# schematic.net
KiCad netlist of a schematic drawn in EAGLE
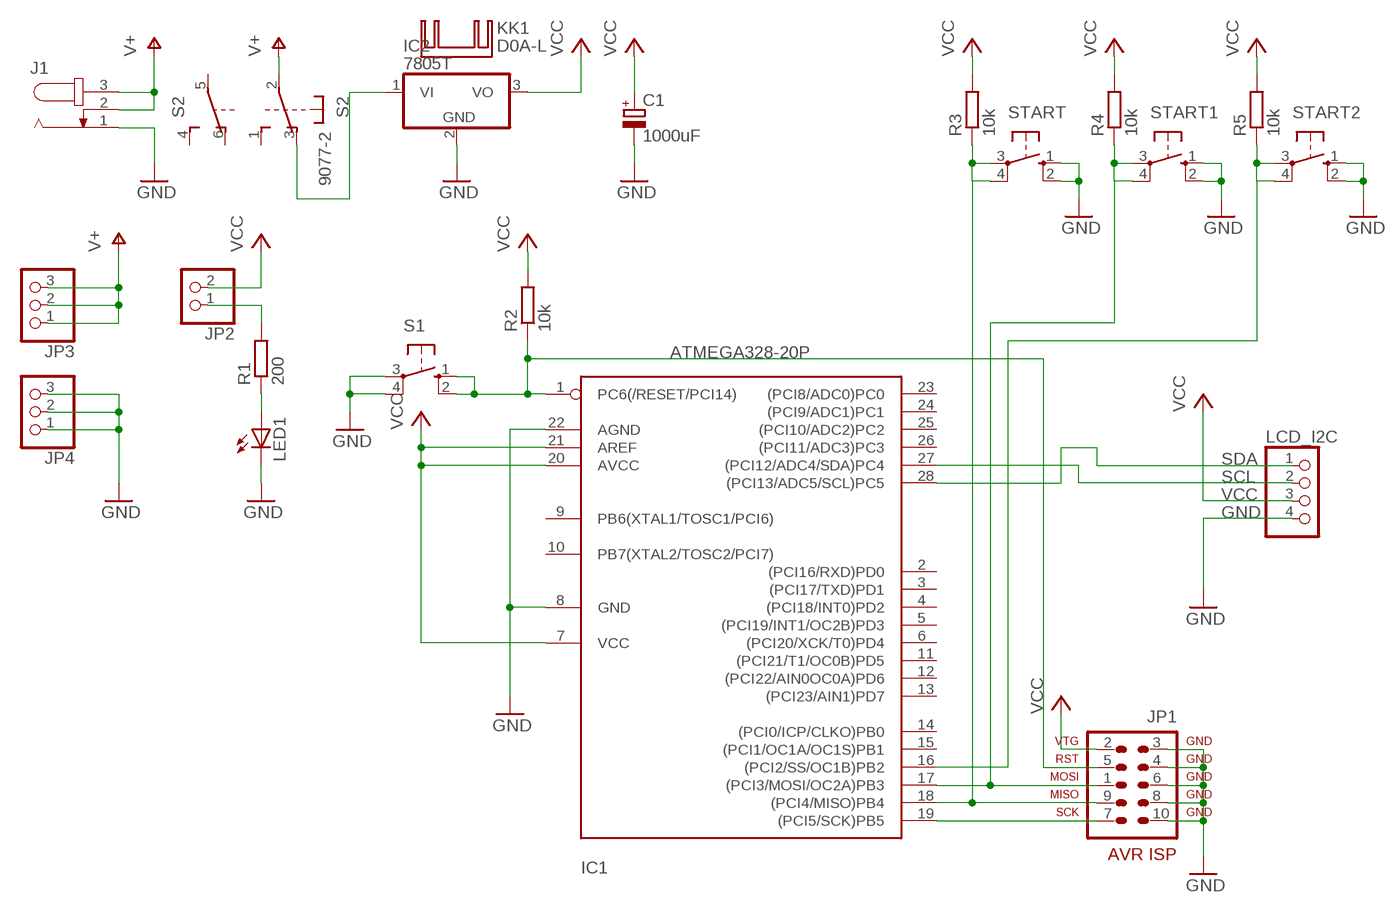
[diagram p0: schematic, sheet 1]

(export (version "E")
  (design (tool "Eeschema 10.0.6"))
  (components
    (comp (ref "C1")
      (value "1000uF")
      (footprint "eagle-import:E3,5-10")
      (libsource (lib "eagle-import") (part "CPOL-EUE3.5-10"))
    )
    (comp (ref "IC1")
      (value "ATMEGA328-20P")
      (footprint "eagle-import:DIL28-3")
      (libsource (lib "eagle-import") (part "ATMEGA328P-20"))
    )
    (comp (ref "IC2")
      (value "7805T")
      (footprint "eagle-import:TO220H")
      (libsource (lib "eagle-import") (part "78T05"))
    )
    (comp (ref "J1")
      (value "JACK-PLUG0")
      (footprint "eagle-import:SPC4077")
      (libsource (lib "eagle-import") (part "JACK-PLUG0"))
    )
    (comp (ref "JP1")
      (value "AVR-ISP-10")
      (footprint "eagle-import:AVR-ISP-10")
      (libsource (lib "eagle-import") (part "AVR-ISP-10"))
    )
    (comp (ref "JP2")
      (value "PINHD-1X2")
      (footprint "eagle-import:1X02")
      (libsource (lib "eagle-import") (part "PINHD-1X2"))
    )
    (comp (ref "JP3")
      (value "PINHD-1X3")
      (footprint "eagle-import:1X03")
      (libsource (lib "eagle-import") (part "PINHD-1X3"))
    )
    (comp (ref "JP4")
      (value "PINHD-1X3")
      (footprint "eagle-import:1X03")
      (libsource (lib "eagle-import") (part "PINHD-1X3"))
    )
    (comp (ref "KK1")
      (value "D0A-L")
      (footprint "eagle-import:D02A-L")
      (libsource (lib "eagle-import") (part "D0A-L"))
    )
    (comp (ref "LCD_I2C")
      (value "PINHD-1X4")
      (footprint "eagle-import:1X04")
      (libsource (lib "eagle-import") (part "PINHD-1X4"))
    )
    (comp (ref "LED1")
      (value "LED5MM")
      (footprint "eagle-import:LED5MM")
      (libsource (lib "eagle-import") (part "LED5MM"))
    )
    (comp (ref "R1")
      (value "200")
      (footprint "eagle-import:0207_10")
      (libsource (lib "eagle-import") (part "R-EU_0207/10"))
    )
    (comp (ref "R2")
      (value "10k")
      (footprint "eagle-import:0207_10")
      (libsource (lib "eagle-import") (part "R-EU_0207/10"))
    )
    (comp (ref "R3")
      (value "10k")
      (footprint "eagle-import:0207_10")
      (libsource (lib "eagle-import") (part "R-EU_0207/10"))
    )
    (comp (ref "R4")
      (value "10k")
      (footprint "eagle-import:0207_10")
      (libsource (lib "eagle-import") (part "R-EU_0207/10"))
    )
    (comp (ref "R5")
      (value "10k")
      (footprint "eagle-import:0207_10")
      (libsource (lib "eagle-import") (part "R-EU_0207/10"))
    )
    (comp (ref "S1")
      (value "10-XX")
      (footprint "eagle-import:B3F-10XX")
      (fields (field (name "MPN") "B3F-1000"))
      (libsource (lib "eagle-import") (part "10-XX"))
    )
    (comp (ref "S2")
      (value "9077-2")
      (footprint "eagle-import:9077-2")
      (libsource (lib "eagle-import") (part "9077-2"))
    )
    (comp (ref "START")
      (value "10-XX")
      (footprint "eagle-import:B3F-10XX")
      (fields (field (name "MPN") "B3F-1000"))
      (libsource (lib "eagle-import") (part "10-XX"))
    )
    (comp (ref "START1")
      (value "10-XX")
      (footprint "eagle-import:B3F-10XX")
      (fields (field (name "MPN") "B3F-1000"))
      (libsource (lib "eagle-import") (part "10-XX"))
    )
    (comp (ref "START2")
      (value "10-XX")
      (footprint "eagle-import:B3F-10XX")
      (fields (field (name "MPN") "B3F-1000"))
      (libsource (lib "eagle-import") (part "10-XX"))
    )
  )
  (nets
    (net (code "1") (name "/SCL") (class "Default")
      (node (ref "IC1") (pin "27") (pinfunction "(PCI12/ADC4/SDA)PC4_27") (pintype "bidirectional"))
      (node (ref "LCD_I2C") (pin "2") (pinfunction "2_2") (pintype "passive"))
    )
    (net (code "2") (name "/SDA") (class "Default")
      (node (ref "IC1") (pin "28") (pinfunction "(PCI13/ADC5/SCL)PC5_28") (pintype "bidirectional"))
      (node (ref "LCD_I2C") (pin "1") (pinfunction "1_1") (pintype "passive"))
    )
    (net (code "3") (name "GND") (class "Default")
      (node (ref "C1") (pin "-") (pinfunction "-_-") (pintype "passive"))
      (node (ref "IC1") (pin "22") (pinfunction "AGND_22") (pintype "bidirectional"))
      (node (ref "IC1") (pin "8") (pinfunction "GND_8") (pintype "bidirectional"))
      (node (ref "IC2") (pin "2") (pinfunction "GND_2") (pintype "passive"))
      (node (ref "J1") (pin "1") (pinfunction "1_1") (pintype "passive"))
      (node (ref "JP1") (pin "10") (pinfunction "10_10") (pintype "passive"))
      (node (ref "JP1") (pin "3") (pinfunction "3_3") (pintype "passive"))
      (node (ref "JP1") (pin "4") (pinfunction "4_4") (pintype "passive"))
      (node (ref "JP1") (pin "6") (pinfunction "6_6") (pintype "passive"))
      (node (ref "JP1") (pin "8") (pinfunction "8_8") (pintype "passive"))
      (node (ref "JP4") (pin "1") (pinfunction "1_1") (pintype "passive"))
      (node (ref "JP4") (pin "2") (pinfunction "2_2") (pintype "passive"))
      (node (ref "JP4") (pin "3") (pinfunction "3_3") (pintype "passive"))
      (node (ref "LCD_I2C") (pin "4") (pinfunction "4_4") (pintype "passive"))
      (node (ref "LED1") (pin "K") (pinfunction "C_K") (pintype "passive"))
      (node (ref "S1") (pin "3") (pinfunction "P_3") (pintype "passive"))
      (node (ref "S1") (pin "4") (pinfunction "P1_4") (pintype "passive"))
      (node (ref "START") (pin "1") (pinfunction "S_1") (pintype "passive"))
      (node (ref "START") (pin "2") (pinfunction "S1_2") (pintype "passive"))
      (node (ref "START1") (pin "1") (pinfunction "S_1") (pintype "passive"))
      (node (ref "START1") (pin "2") (pinfunction "S1_2") (pintype "passive"))
      (node (ref "START2") (pin "1") (pinfunction "S_1") (pintype "passive"))
      (node (ref "START2") (pin "2") (pinfunction "S1_2") (pintype "passive"))
    )
    (net (code "4") (name "Net-(IC1-(PCI2{slash}SS{slash}OC1B)PB2)") (class "Default")
      (node (ref "IC1") (pin "16") (pinfunction "(PCI2/SS/OC1B)PB2_16") (pintype "bidirectional"))
      (node (ref "R5") (pin "1") (pinfunction "1_1") (pintype "passive"))
      (node (ref "START2") (pin "3") (pinfunction "P_3") (pintype "passive"))
      (node (ref "START2") (pin "4") (pinfunction "P1_4") (pintype "passive"))
    )
    (net (code "5") (name "Net-(IC1-(PCI3{slash}MOSI{slash}OC2A)PB3)") (class "Default")
      (node (ref "IC1") (pin "17") (pinfunction "(PCI3/MOSI/OC2A)PB3_17") (pintype "bidirectional"))
      (node (ref "JP1") (pin "1") (pinfunction "1_1") (pintype "passive"))
      (node (ref "R4") (pin "1") (pinfunction "1_1") (pintype "passive"))
      (node (ref "START1") (pin "3") (pinfunction "P_3") (pintype "passive"))
      (node (ref "START1") (pin "4") (pinfunction "P1_4") (pintype "passive"))
    )
    (net (code "6") (name "Net-(IC1-(PCI4{slash}MISO)PB4)") (class "Default")
      (node (ref "IC1") (pin "18") (pinfunction "(PCI4/MISO)PB4_18") (pintype "bidirectional"))
      (node (ref "JP1") (pin "9") (pinfunction "9_9") (pintype "passive"))
      (node (ref "R3") (pin "1") (pinfunction "1_1") (pintype "passive"))
      (node (ref "START") (pin "3") (pinfunction "P_3") (pintype "passive"))
      (node (ref "START") (pin "4") (pinfunction "P1_4") (pintype "passive"))
    )
    (net (code "7") (name "Net-(IC1-(PCI5{slash}SCK)PB5)") (class "Default")
      (node (ref "IC1") (pin "19") (pinfunction "(PCI5/SCK)PB5_19") (pintype "bidirectional"))
      (node (ref "JP1") (pin "7") (pinfunction "7_7") (pintype "passive"))
    )
    (net (code "8") (name "Net-(IC1-PC6({slash}RESET{slash}PCI14))") (class "Default")
      (node (ref "IC1") (pin "1") (pinfunction "PC6(/RESET/PCI14)_1") (pintype "bidirectional"))
      (node (ref "JP1") (pin "5") (pinfunction "5_5") (pintype "passive"))
      (node (ref "R2") (pin "1") (pinfunction "1_1") (pintype "passive"))
      (node (ref "S1") (pin "1") (pinfunction "S_1") (pintype "passive"))
      (node (ref "S1") (pin "2") (pinfunction "S1_2") (pintype "passive"))
    )
    (net (code "9") (name "Net-(IC2-VI)") (class "Default")
      (node (ref "IC2") (pin "1") (pinfunction "VI_1") (pintype "input"))
      (node (ref "S2") (pin "3") (pinfunction "O_3") (pintype "passive"))
    )
    (net (code "10") (name "Net-(JP2-Pad1)") (class "Default")
      (node (ref "JP2") (pin "1") (pinfunction "1_1") (pintype "passive"))
      (node (ref "R1") (pin "2") (pinfunction "2_2") (pintype "passive"))
    )
    (net (code "11") (name "Net-(LED1-PadA)") (class "Default")
      (node (ref "LED1") (pin "A") (pinfunction "A_A") (pintype "passive"))
      (node (ref "R1") (pin "1") (pinfunction "1_1") (pintype "passive"))
    )
    (net (code "12") (name "V+") (class "Default")
      (node (ref "J1") (pin "2") (pinfunction "2_2") (pintype "passive"))
      (node (ref "J1") (pin "3") (pinfunction "3_3") (pintype "passive"))
      (node (ref "JP3") (pin "1") (pinfunction "1_1") (pintype "passive"))
      (node (ref "JP3") (pin "2") (pinfunction "2_2") (pintype "passive"))
      (node (ref "JP3") (pin "3") (pinfunction "3_3") (pintype "passive"))
      (node (ref "S2") (pin "2") (pinfunction "P_2") (pintype "passive"))
    )
    (net (code "13") (name "VCC") (class "Default")
      (node (ref "C1") (pin "+") (pinfunction "+_+") (pintype "passive"))
      (node (ref "IC1") (pin "20") (pinfunction "AVCC_20") (pintype "bidirectional"))
      (node (ref "IC1") (pin "21") (pinfunction "AREF_21") (pintype "bidirectional"))
      (node (ref "IC1") (pin "7") (pinfunction "VCC_7") (pintype "bidirectional"))
      (node (ref "IC2") (pin "3") (pinfunction "VO_3") (pintype "passive"))
      (node (ref "JP1") (pin "2") (pinfunction "2_2") (pintype "passive"))
      (node (ref "JP2") (pin "2") (pinfunction "2_2") (pintype "passive"))
      (node (ref "LCD_I2C") (pin "3") (pinfunction "3_3") (pintype "passive"))
      (node (ref "R2") (pin "2") (pinfunction "2_2") (pintype "passive"))
      (node (ref "R3") (pin "2") (pinfunction "2_2") (pintype "passive"))
      (node (ref "R4") (pin "2") (pinfunction "2_2") (pintype "passive"))
      (node (ref "R5") (pin "2") (pinfunction "2_2") (pintype "passive"))
    )
    (net (code "14") (name "unconnected-(IC1-(PCI0{slash}ICP{slash}CLKO)PB0-Pad14)") (class "Default")
      (node (ref "IC1") (pin "14") (pinfunction "(PCI0/ICP/CLKO)PB0_14") (pintype "bidirectional"))
    )
    (net (code "15") (name "unconnected-(IC1-(PCI1{slash}OC1A{slash}OC1S)PB1-Pad15)") (class "Default")
      (node (ref "IC1") (pin "15") (pinfunction "(PCI1/OC1A/OC1S)PB1_15") (pintype "bidirectional"))
    )
    (net (code "16") (name "unconnected-(IC1-(PCI8{slash}ADC0)PC0-Pad23)") (class "Default")
      (node (ref "IC1") (pin "23") (pinfunction "(PCI8/ADC0)PC0_23") (pintype "bidirectional"))
    )
    (net (code "17") (name "unconnected-(IC1-(PCI9{slash}ADC1)PC1-Pad24)") (class "Default")
      (node (ref "IC1") (pin "24") (pinfunction "(PCI9/ADC1)PC1_24") (pintype "bidirectional"))
    )
    (net (code "18") (name "unconnected-(IC1-(PCI10{slash}ADC2)PC2-Pad25)") (class "Default")
      (node (ref "IC1") (pin "25") (pinfunction "(PCI10/ADC2)PC2_25") (pintype "bidirectional"))
    )
    (net (code "19") (name "unconnected-(IC1-(PCI11{slash}ADC3)PC3-Pad26)") (class "Default")
      (node (ref "IC1") (pin "26") (pinfunction "(PCI11/ADC3)PC3_26") (pintype "bidirectional"))
    )
    (net (code "20") (name "unconnected-(IC1-(PCI16{slash}RXD)PD0-Pad2)") (class "Default")
      (node (ref "IC1") (pin "2") (pinfunction "(PCI16/RXD)PD0_2") (pintype "bidirectional"))
    )
    (net (code "21") (name "unconnected-(IC1-(PCI17{slash}TXD)PD1-Pad3)") (class "Default")
      (node (ref "IC1") (pin "3") (pinfunction "(PCI17/TXD)PD1_3") (pintype "bidirectional"))
    )
    (net (code "22") (name "unconnected-(IC1-(PCI18{slash}INT0)PD2-Pad4)") (class "Default")
      (node (ref "IC1") (pin "4") (pinfunction "(PCI18/INT0)PD2_4") (pintype "bidirectional"))
    )
    (net (code "23") (name "unconnected-(IC1-(PCI19{slash}INT1{slash}OC2B)PD3-Pad5)") (class "Default")
      (node (ref "IC1") (pin "5") (pinfunction "(PCI19/INT1/OC2B)PD3_5") (pintype "bidirectional"))
    )
    (net (code "24") (name "unconnected-(IC1-(PCI20{slash}XCK{slash}T0)PD4-Pad6)") (class "Default")
      (node (ref "IC1") (pin "6") (pinfunction "(PCI20/XCK/T0)PD4_6") (pintype "bidirectional"))
    )
    (net (code "25") (name "unconnected-(IC1-(PCI21{slash}T1{slash}OC0B)PD5-Pad11)") (class "Default")
      (node (ref "IC1") (pin "11") (pinfunction "(PCI21/T1/OC0B)PD5_11") (pintype "bidirectional"))
    )
    (net (code "26") (name "unconnected-(IC1-(PCI22{slash}AIN0OC0A)PD6-Pad12)") (class "Default")
      (node (ref "IC1") (pin "12") (pinfunction "(PCI22/AIN0OC0A)PD6_12") (pintype "bidirectional"))
    )
    (net (code "27") (name "unconnected-(IC1-(PCI23{slash}AIN1)PD7-Pad13)") (class "Default")
      (node (ref "IC1") (pin "13") (pinfunction "(PCI23/AIN1)PD7_13") (pintype "bidirectional"))
    )
    (net (code "28") (name "unconnected-(IC1-PB6(XTAL1{slash}TOSC1{slash}PCI6)-Pad9)") (class "Default")
      (node (ref "IC1") (pin "9") (pinfunction "PB6(XTAL1/TOSC1/PCI6)_9") (pintype "bidirectional"))
    )
    (net (code "29") (name "unconnected-(IC1-PB7(XTAL2{slash}TOSC2{slash}PCI7)-Pad10)") (class "Default")
      (node (ref "IC1") (pin "10") (pinfunction "PB7(XTAL2/TOSC2/PCI7)_10") (pintype "bidirectional"))
    )
    (net (code "30") (name "unconnected-(S2A-S-Pad1)") (class "Default")
      (node (ref "S2") (pin "1") (pinfunction "S_1") (pintype "passive"))
    )
    (net (code "31") (name "unconnected-(S2B-O-Pad6)") (class "Default")
      (node (ref "S2") (pin "6") (pinfunction "O_6") (pintype "passive"))
    )
    (net (code "32") (name "unconnected-(S2B-P-Pad5)") (class "Default")
      (node (ref "S2") (pin "5") (pinfunction "P_5") (pintype "passive"))
    )
    (net (code "33") (name "unconnected-(S2B-S-Pad4)") (class "Default")
      (node (ref "S2") (pin "4") (pinfunction "S_4") (pintype "passive"))
    )
  )
)
